# RotaryEncoderModule_r1.net
KiCad netlist of a schematic drawn in EAGLE
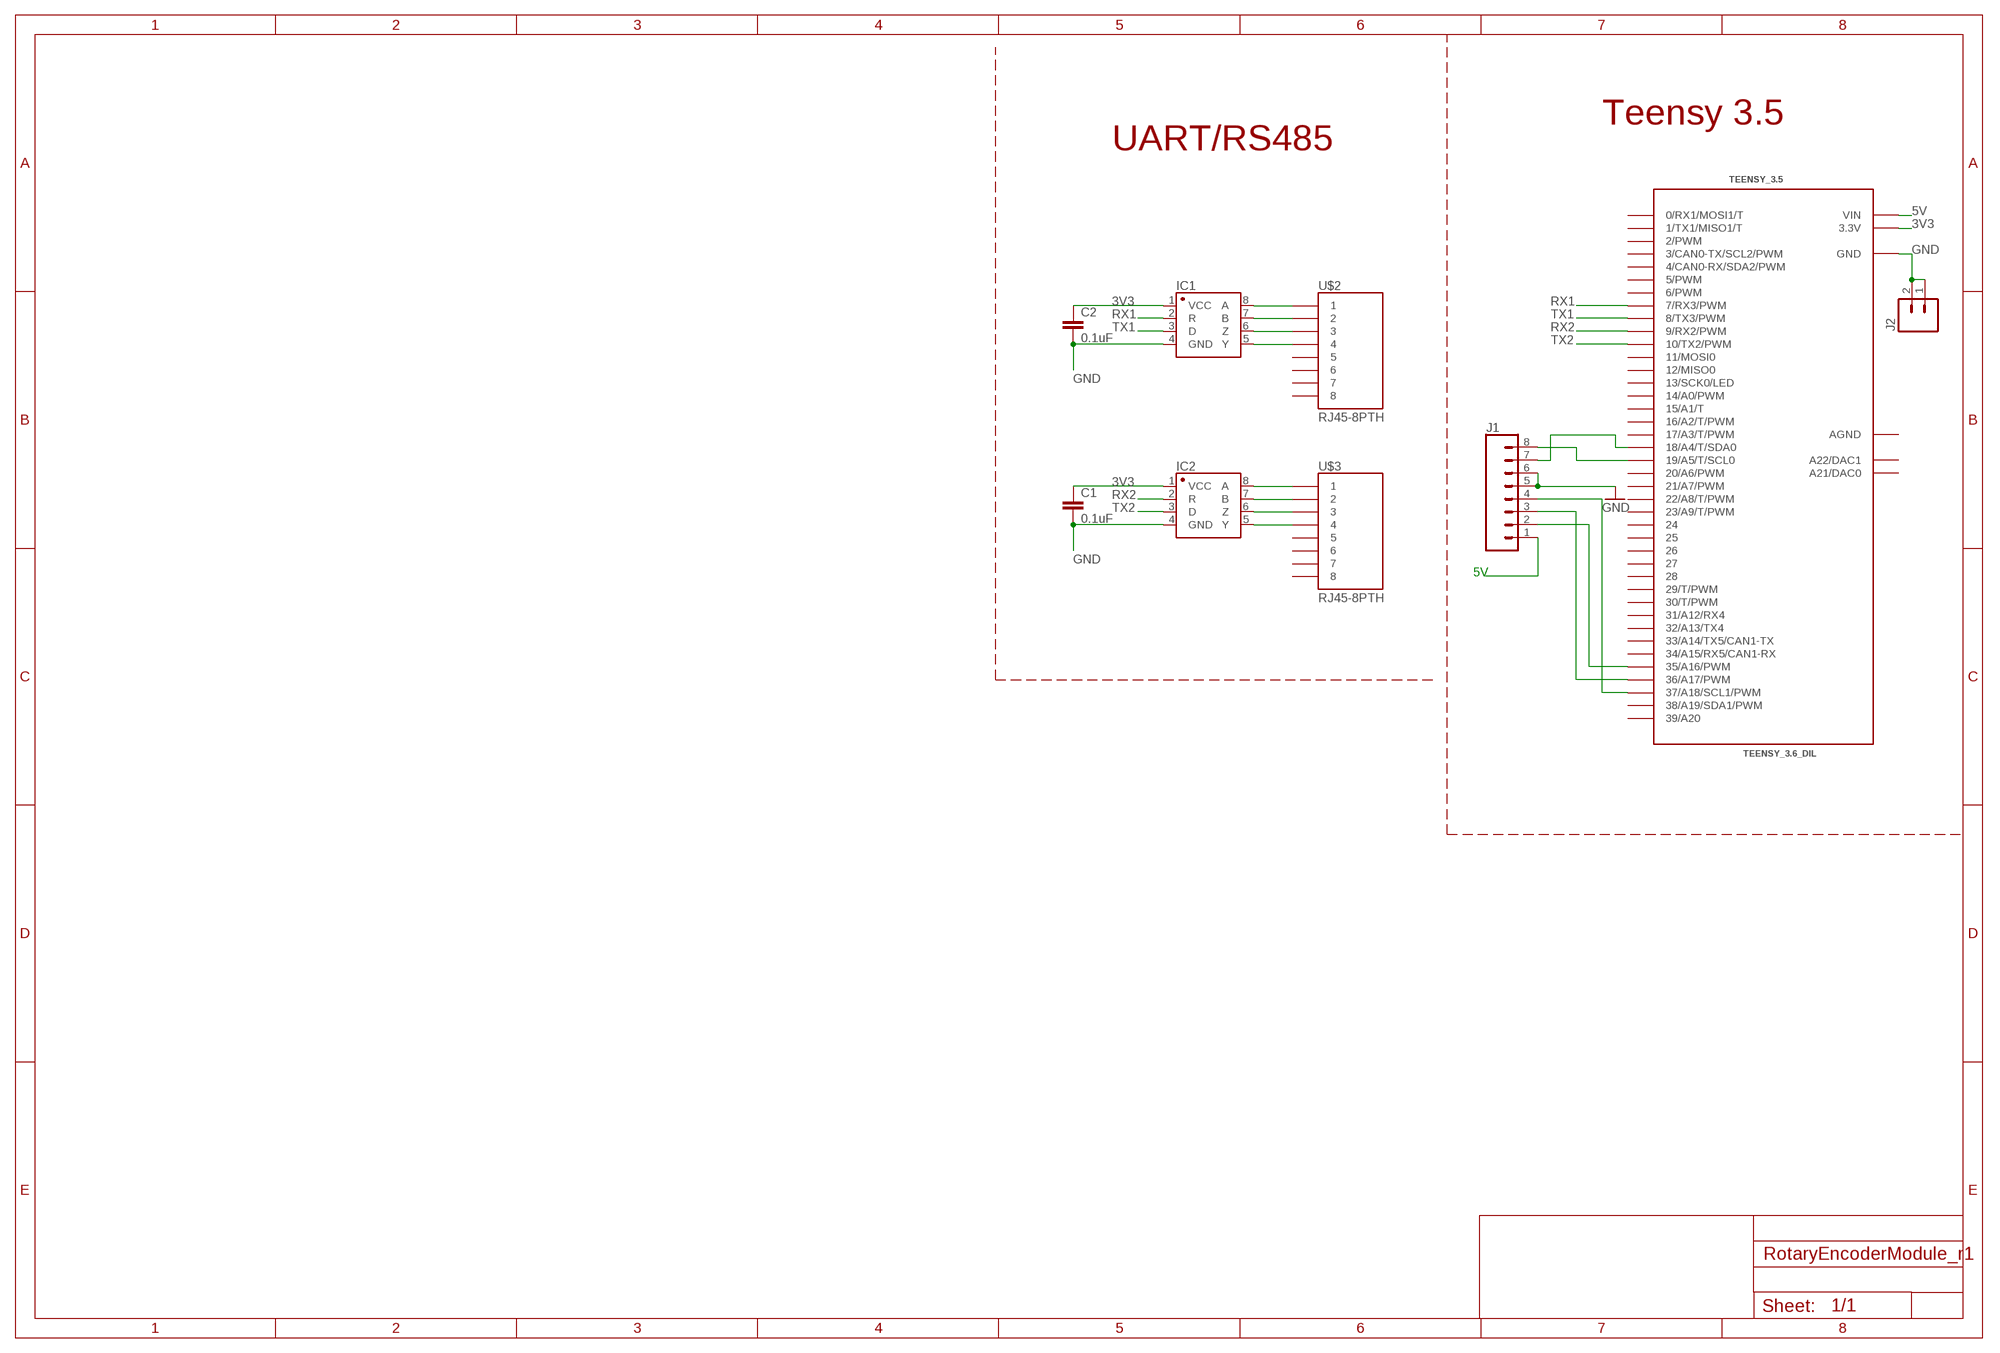
[diagram p0: schematic, sheet 1]

(export (version "E")
  (design (tool "Eeschema 10.0.6"))
  (components
    (comp (ref "C1")
      (value "0.1uF")
      (footprint "eagle-import:1206")
      (libsource (lib "eagle-import") (part "1.0UF-1206-50V-10%"))
    )
    (comp (ref "C2")
      (value "0.1uF")
      (footprint "eagle-import:1206")
      (libsource (lib "eagle-import") (part "1.0UF-1206-50V-10%"))
    )
    (comp (ref "IC1")
      (value "SN65HVD31DR")
      (footprint "eagle-import:SO08")
      (libsource (lib "eagle-import") (part "SN65HVD31DR"))
    )
    (comp (ref "IC2")
      (value "SN65HVD31DR")
      (footprint "eagle-import:SO08")
      (libsource (lib "eagle-import") (part "SN65HVD31DR"))
    )
    (comp (ref "J1")
      (value "CONN_083.5MM-8")
      (footprint "eagle-import:SCREWTERMINAL-3.5MM-8")
      (libsource (lib "eagle-import") (part "CONN_083.5MM-8"))
    )
    (comp (ref "J2")
      (value "M023.5MM")
      (footprint "eagle-import:SCREWTERMINAL-3.5MM-2")
      (libsource (lib "eagle-import") (part "M023.5MM"))
    )
    (comp (ref "TEENSY_3.5")
      (value "TEENSY_3.6_DIL")
      (footprint "eagle-import:TEENSY_3.6_DIL")
      (libsource (lib "eagle-import") (part "TEENSY_3.6_DIL"))
    )
    (comp (ref "U$2")
      (value "RJ45-8PTH")
      (footprint "eagle-import:RJ45-8")
      (libsource (lib "eagle-import") (part "RJ45-8PTH"))
    )
    (comp (ref "U$3")
      (value "RJ45-8PTH")
      (footprint "eagle-import:RJ45-8")
      (libsource (lib "eagle-import") (part "RJ45-8PTH"))
    )
  )
  (nets
    (net (code "1") (name "/3V3") (class "Default")
      (node (ref "C1") (pin "1") (pinfunction "1_1") (pintype "passive"))
      (node (ref "C2") (pin "1") (pinfunction "1_1") (pintype "passive"))
      (node (ref "IC1") (pin "1") (pinfunction "VCC_1") (pintype "bidirectional"))
      (node (ref "IC2") (pin "1") (pinfunction "VCC_1") (pintype "bidirectional"))
      (node (ref "TEENSY_3.5") (pin "3.3V") (pinfunction "3.3V_3.3V") (pintype "power_in"))
      (node (ref "TEENSY_3.5") (pin "3.3V3") (pinfunction "3.3V_3.3V3") (pintype "power_in"))
    )
    (net (code "2") (name "/5V") (class "Default")
      (node (ref "J1") (pin "1") (pinfunction "1_1") (pintype "passive"))
      (node (ref "TEENSY_3.5") (pin "VIN") (pinfunction "VIN_VIN") (pintype "power_in"))
    )
    (net (code "3") (name "/AGND") (class "Default")
      (node (ref "TEENSY_3.5") (pin "AGND") (pinfunction "AGND_AGND") (pintype "power_in"))
    )
    (net (code "4") (name "/RX1") (class "Default")
      (node (ref "IC1") (pin "2") (pinfunction "R_2") (pintype "bidirectional"))
      (node (ref "TEENSY_3.5") (pin "7") (pinfunction "7/RX3/PWM_7") (pintype "bidirectional"))
    )
    (net (code "5") (name "/RX2") (class "Default")
      (node (ref "IC2") (pin "2") (pinfunction "R_2") (pintype "bidirectional"))
      (node (ref "TEENSY_3.5") (pin "9") (pinfunction "9/RX2/PWM_9") (pintype "bidirectional"))
    )
    (net (code "6") (name "/TX1") (class "Default")
      (node (ref "IC1") (pin "3") (pinfunction "D_3") (pintype "bidirectional"))
      (node (ref "TEENSY_3.5") (pin "8") (pinfunction "8/TX3/PWM_8") (pintype "bidirectional"))
    )
    (net (code "7") (name "/TX2") (class "Default")
      (node (ref "IC2") (pin "3") (pinfunction "D_3") (pintype "bidirectional"))
      (node (ref "TEENSY_3.5") (pin "10") (pinfunction "10/TX2/PWM_10") (pintype "bidirectional"))
    )
    (net (code "8") (name "GND") (class "Default")
      (node (ref "C1") (pin "2") (pinfunction "2_2") (pintype "passive"))
      (node (ref "C2") (pin "2") (pinfunction "2_2") (pintype "passive"))
      (node (ref "IC1") (pin "4") (pinfunction "GND_4") (pintype "bidirectional"))
      (node (ref "IC2") (pin "4") (pinfunction "GND_4") (pintype "bidirectional"))
      (node (ref "J1") (pin "5") (pinfunction "5_5") (pintype "passive"))
      (node (ref "J1") (pin "6") (pinfunction "6_6") (pintype "passive"))
      (node (ref "J2") (pin "1") (pinfunction "1_1") (pintype "passive"))
      (node (ref "J2") (pin "2") (pinfunction "2_2") (pintype "passive"))
      (node (ref "TEENSY_3.5") (pin "GND") (pinfunction "GND_GND") (pintype "power_in"))
      (node (ref "TEENSY_3.5") (pin "GND1") (pinfunction "GND_GND1") (pintype "power_in"))
    )
    (net (code "9") (name "Net-(IC1-A)") (class "Default")
      (node (ref "IC1") (pin "8") (pinfunction "A_8") (pintype "bidirectional"))
      (node (ref "U$2") (pin "1") (pinfunction "1_1") (pintype "bidirectional"))
    )
    (net (code "10") (name "Net-(IC1-B)") (class "Default")
      (node (ref "IC1") (pin "7") (pinfunction "B_7") (pintype "bidirectional"))
      (node (ref "U$2") (pin "2") (pinfunction "2_2") (pintype "bidirectional"))
    )
    (net (code "11") (name "Net-(IC1-Y)") (class "Default")
      (node (ref "IC1") (pin "5") (pinfunction "Y_5") (pintype "bidirectional"))
      (node (ref "U$2") (pin "4") (pinfunction "4_4") (pintype "bidirectional"))
    )
    (net (code "12") (name "Net-(IC1-Z)") (class "Default")
      (node (ref "IC1") (pin "6") (pinfunction "Z_6") (pintype "bidirectional"))
      (node (ref "U$2") (pin "3") (pinfunction "3_3") (pintype "bidirectional"))
    )
    (net (code "13") (name "Net-(IC2-A)") (class "Default")
      (node (ref "IC2") (pin "8") (pinfunction "A_8") (pintype "bidirectional"))
      (node (ref "U$3") (pin "1") (pinfunction "1_1") (pintype "bidirectional"))
    )
    (net (code "14") (name "Net-(IC2-B)") (class "Default")
      (node (ref "IC2") (pin "7") (pinfunction "B_7") (pintype "bidirectional"))
      (node (ref "U$3") (pin "2") (pinfunction "2_2") (pintype "bidirectional"))
    )
    (net (code "15") (name "Net-(IC2-Y)") (class "Default")
      (node (ref "IC2") (pin "5") (pinfunction "Y_5") (pintype "bidirectional"))
      (node (ref "U$3") (pin "4") (pinfunction "4_4") (pintype "bidirectional"))
    )
    (net (code "16") (name "Net-(IC2-Z)") (class "Default")
      (node (ref "IC2") (pin "6") (pinfunction "Z_6") (pintype "bidirectional"))
      (node (ref "U$3") (pin "3") (pinfunction "3_3") (pintype "bidirectional"))
    )
    (net (code "17") (name "Net-(TEENSY_3.5-18{slash}A4{slash}T{slash}SDA0)") (class "Default")
      (node (ref "J1") (pin "7") (pinfunction "7_7") (pintype "passive"))
      (node (ref "TEENSY_3.5") (pin "18/A4") (pinfunction "18/A4/T/SDA0_18/A4") (pintype "bidirectional"))
    )
    (net (code "18") (name "Net-(TEENSY_3.5-19{slash}A5{slash}T{slash}SCL0)") (class "Default")
      (node (ref "J1") (pin "8") (pinfunction "8_8") (pintype "passive"))
      (node (ref "TEENSY_3.5") (pin "19/A5") (pinfunction "19/A5/T/SCL0_19/A5") (pintype "bidirectional"))
    )
    (net (code "19") (name "Net-(TEENSY_3.5-35{slash}A16{slash}PWM)") (class "Default")
      (node (ref "J1") (pin "2") (pinfunction "2_2") (pintype "passive"))
      (node (ref "TEENSY_3.5") (pin "35/A16") (pinfunction "35/A16/PWM_35/A16") (pintype "bidirectional"))
    )
    (net (code "20") (name "Net-(TEENSY_3.5-36{slash}A17{slash}PWM)") (class "Default")
      (node (ref "J1") (pin "3") (pinfunction "3_3") (pintype "passive"))
      (node (ref "TEENSY_3.5") (pin "36/A17") (pinfunction "36/A17/PWM_36/A17") (pintype "bidirectional"))
    )
    (net (code "21") (name "Net-(TEENSY_3.5-37{slash}A18{slash}SCL1{slash}PWM)") (class "Default")
      (node (ref "J1") (pin "4") (pinfunction "4_4") (pintype "passive"))
      (node (ref "TEENSY_3.5") (pin "37/A18") (pinfunction "37/A18/SCL1/PWM_37/A18") (pintype "bidirectional"))
    )
    (net (code "22") (name "unconnected-(TEENSY_3.5-0{slash}RX1{slash}MOSI1{slash}T-Pad0)") (class "Default")
      (node (ref "TEENSY_3.5") (pin "0") (pinfunction "0/RX1/MOSI1/T_0") (pintype "bidirectional"))
    )
    (net (code "23") (name "unconnected-(TEENSY_3.5-1{slash}TX1{slash}MISO1{slash}T-Pad1)") (class "Default")
      (node (ref "TEENSY_3.5") (pin "1") (pinfunction "1/TX1/MISO1/T_1") (pintype "bidirectional"))
    )
    (net (code "24") (name "unconnected-(TEENSY_3.5-2{slash}PWM-Pad2)") (class "Default")
      (node (ref "TEENSY_3.5") (pin "2") (pinfunction "2/PWM_2") (pintype "bidirectional"))
    )
    (net (code "25") (name "unconnected-(TEENSY_3.5-3{slash}CAN0-TX{slash}SCL2{slash}PWM-Pad3)") (class "Default")
      (node (ref "TEENSY_3.5") (pin "3") (pinfunction "3/CAN0-TX/SCL2/PWM_3") (pintype "bidirectional"))
    )
    (net (code "26") (name "unconnected-(TEENSY_3.5-4{slash}CAN0-RX{slash}SDA2{slash}PWM-Pad4)") (class "Default")
      (node (ref "TEENSY_3.5") (pin "4") (pinfunction "4/CAN0-RX/SDA2/PWM_4") (pintype "bidirectional"))
    )
    (net (code "27") (name "unconnected-(TEENSY_3.5-5{slash}PWM-Pad5)") (class "Default")
      (node (ref "TEENSY_3.5") (pin "5") (pinfunction "5/PWM_5") (pintype "bidirectional"))
    )
    (net (code "28") (name "unconnected-(TEENSY_3.5-6{slash}PWM-Pad6)") (class "Default")
      (node (ref "TEENSY_3.5") (pin "6") (pinfunction "6/PWM_6") (pintype "bidirectional"))
    )
    (net (code "29") (name "unconnected-(TEENSY_3.5-11{slash}MOSI0-Pad11)") (class "Default")
      (node (ref "TEENSY_3.5") (pin "11") (pinfunction "11/MOSI0_11") (pintype "bidirectional"))
    )
    (net (code "30") (name "unconnected-(TEENSY_3.5-12{slash}MISO0-Pad12)") (class "Default")
      (node (ref "TEENSY_3.5") (pin "12") (pinfunction "12/MISO0_12") (pintype "bidirectional"))
    )
    (net (code "31") (name "unconnected-(TEENSY_3.5-13{slash}SCK0{slash}LED-Pad13)") (class "Default")
      (node (ref "TEENSY_3.5") (pin "13") (pinfunction "13/SCK0/LED_13") (pintype "bidirectional"))
    )
    (net (code "32") (name "unconnected-(TEENSY_3.5-14{slash}A0{slash}PWM-Pad14{slash}A0)") (class "Default")
      (node (ref "TEENSY_3.5") (pin "14/A0") (pinfunction "14/A0/PWM_14/A0") (pintype "bidirectional"))
    )
    (net (code "33") (name "unconnected-(TEENSY_3.5-15{slash}A1{slash}T-Pad15{slash}A1)") (class "Default")
      (node (ref "TEENSY_3.5") (pin "15/A1") (pinfunction "15/A1/T_15/A1") (pintype "bidirectional"))
    )
    (net (code "34") (name "unconnected-(TEENSY_3.5-16{slash}A2{slash}T{slash}PWM-Pad16{slash}A2)") (class "Default")
      (node (ref "TEENSY_3.5") (pin "16/A2") (pinfunction "16/A2/T/PWM_16/A2") (pintype "bidirectional"))
    )
    (net (code "35") (name "unconnected-(TEENSY_3.5-17{slash}A3{slash}T{slash}PWM-Pad17{slash}A3)") (class "Default")
      (node (ref "TEENSY_3.5") (pin "17/A3") (pinfunction "17/A3/T/PWM_17/A3") (pintype "bidirectional"))
    )
    (net (code "36") (name "unconnected-(TEENSY_3.5-20{slash}A6{slash}PWM-Pad20{slash}A6)") (class "Default")
      (node (ref "TEENSY_3.5") (pin "20/A6") (pinfunction "20/A6/PWM_20/A6") (pintype "bidirectional"))
    )
    (net (code "37") (name "unconnected-(TEENSY_3.5-21{slash}A7{slash}PWM-Pad21{slash}A7)") (class "Default")
      (node (ref "TEENSY_3.5") (pin "21/A7") (pinfunction "21/A7/PWM_21/A7") (pintype "bidirectional"))
    )
    (net (code "38") (name "unconnected-(TEENSY_3.5-22{slash}A8{slash}T{slash}PWM-Pad22{slash}A8)") (class "Default")
      (node (ref "TEENSY_3.5") (pin "22/A8") (pinfunction "22/A8/T/PWM_22/A8") (pintype "bidirectional"))
    )
    (net (code "39") (name "unconnected-(TEENSY_3.5-23{slash}A9{slash}T{slash}PWM-Pad23{slash}A9)") (class "Default")
      (node (ref "TEENSY_3.5") (pin "23/A9") (pinfunction "23/A9/T/PWM_23/A9") (pintype "bidirectional"))
    )
    (net (code "40") (name "unconnected-(TEENSY_3.5-29{slash}T{slash}PWM-Pad29)") (class "Default")
      (node (ref "TEENSY_3.5") (pin "29") (pinfunction "29/T/PWM_29") (pintype "bidirectional"))
    )
    (net (code "41") (name "unconnected-(TEENSY_3.5-30{slash}T{slash}PWM-Pad30)") (class "Default")
      (node (ref "TEENSY_3.5") (pin "30") (pinfunction "30/T/PWM_30") (pintype "bidirectional"))
    )
    (net (code "42") (name "unconnected-(TEENSY_3.5-31{slash}A12{slash}RX4-Pad31{slash}A12)") (class "Default")
      (node (ref "TEENSY_3.5") (pin "31/A12") (pinfunction "31/A12/RX4_31/A12") (pintype "bidirectional"))
    )
    (net (code "43") (name "unconnected-(TEENSY_3.5-32{slash}A13{slash}TX4-Pad32{slash}A13)") (class "Default")
      (node (ref "TEENSY_3.5") (pin "32/A13") (pinfunction "32/A13/TX4_32/A13") (pintype "bidirectional"))
    )
    (net (code "44") (name "unconnected-(TEENSY_3.5-33{slash}A14{slash}TX5{slash}CAN1-TX-Pad33{slash}A14)") (class "Default")
      (node (ref "TEENSY_3.5") (pin "33/A14") (pinfunction "33/A14/TX5/CAN1-TX_33/A14") (pintype "bidirectional"))
    )
    (net (code "45") (name "unconnected-(TEENSY_3.5-34{slash}A15{slash}RX5{slash}CAN1-RX-Pad34{slash}A15)") (class "Default")
      (node (ref "TEENSY_3.5") (pin "34/A15") (pinfunction "34/A15/RX5/CAN1-RX_34/A15") (pintype "bidirectional"))
    )
    (net (code "46") (name "unconnected-(TEENSY_3.5-38{slash}A19{slash}SDA1{slash}PWM-Pad38{slash}A19)") (class "Default")
      (node (ref "TEENSY_3.5") (pin "38/A19") (pinfunction "38/A19/SDA1/PWM_38/A19") (pintype "bidirectional"))
    )
    (net (code "47") (name "unconnected-(TEENSY_3.5-A21{slash}DAC0-PadA21)") (class "Default")
      (node (ref "TEENSY_3.5") (pin "A21") (pinfunction "A21/DAC0_A21") (pintype "bidirectional"))
    )
    (net (code "48") (name "unconnected-(TEENSY_3.5-A22{slash}DAC1-PadA22)") (class "Default")
      (node (ref "TEENSY_3.5") (pin "A22") (pinfunction "A22/DAC1_A22") (pintype "bidirectional"))
    )
    (net (code "49") (name "unconnected-(TEENSY_3.5-Pad24)") (class "Default")
      (node (ref "TEENSY_3.5") (pin "24") (pinfunction "24_24") (pintype "bidirectional"))
    )
    (net (code "50") (name "unconnected-(TEENSY_3.5-Pad25)") (class "Default")
      (node (ref "TEENSY_3.5") (pin "25") (pinfunction "25_25") (pintype "bidirectional"))
    )
    (net (code "51") (name "unconnected-(TEENSY_3.5-Pad26)") (class "Default")
      (node (ref "TEENSY_3.5") (pin "26") (pinfunction "26_26") (pintype "bidirectional"))
    )
    (net (code "52") (name "unconnected-(TEENSY_3.5-Pad27)") (class "Default")
      (node (ref "TEENSY_3.5") (pin "27") (pinfunction "27_27") (pintype "bidirectional"))
    )
    (net (code "53") (name "unconnected-(TEENSY_3.5-Pad28)") (class "Default")
      (node (ref "TEENSY_3.5") (pin "28") (pinfunction "28_28") (pintype "bidirectional"))
    )
    (net (code "54") (name "unconnected-(TEENSY_3.5-Pad39{slash}A20)") (class "Default")
      (node (ref "TEENSY_3.5") (pin "39/A20") (pinfunction "39/A20_39/A20") (pintype "bidirectional"))
    )
    (net (code "55") (name "unconnected-(U$2-Pad5)") (class "Default")
      (node (ref "U$2") (pin "5") (pinfunction "5_5") (pintype "bidirectional"))
    )
    (net (code "56") (name "unconnected-(U$2-Pad6)") (class "Default")
      (node (ref "U$2") (pin "6") (pinfunction "6_6") (pintype "bidirectional"))
    )
    (net (code "57") (name "unconnected-(U$2-Pad7)") (class "Default")
      (node (ref "U$2") (pin "7") (pinfunction "7_7") (pintype "bidirectional"))
    )
    (net (code "58") (name "unconnected-(U$2-Pad8)") (class "Default")
      (node (ref "U$2") (pin "8") (pinfunction "8_8") (pintype "bidirectional"))
    )
    (net (code "59") (name "unconnected-(U$3-Pad5)") (class "Default")
      (node (ref "U$3") (pin "5") (pinfunction "5_5") (pintype "bidirectional"))
    )
    (net (code "60") (name "unconnected-(U$3-Pad6)") (class "Default")
      (node (ref "U$3") (pin "6") (pinfunction "6_6") (pintype "bidirectional"))
    )
    (net (code "61") (name "unconnected-(U$3-Pad7)") (class "Default")
      (node (ref "U$3") (pin "7") (pinfunction "7_7") (pintype "bidirectional"))
    )
    (net (code "62") (name "unconnected-(U$3-Pad8)") (class "Default")
      (node (ref "U$3") (pin "8") (pinfunction "8_8") (pintype "bidirectional"))
    )
  )
)
